# PX4FMUv2_4_6_11.net
KiCad netlist of a schematic drawn in Altium Designer
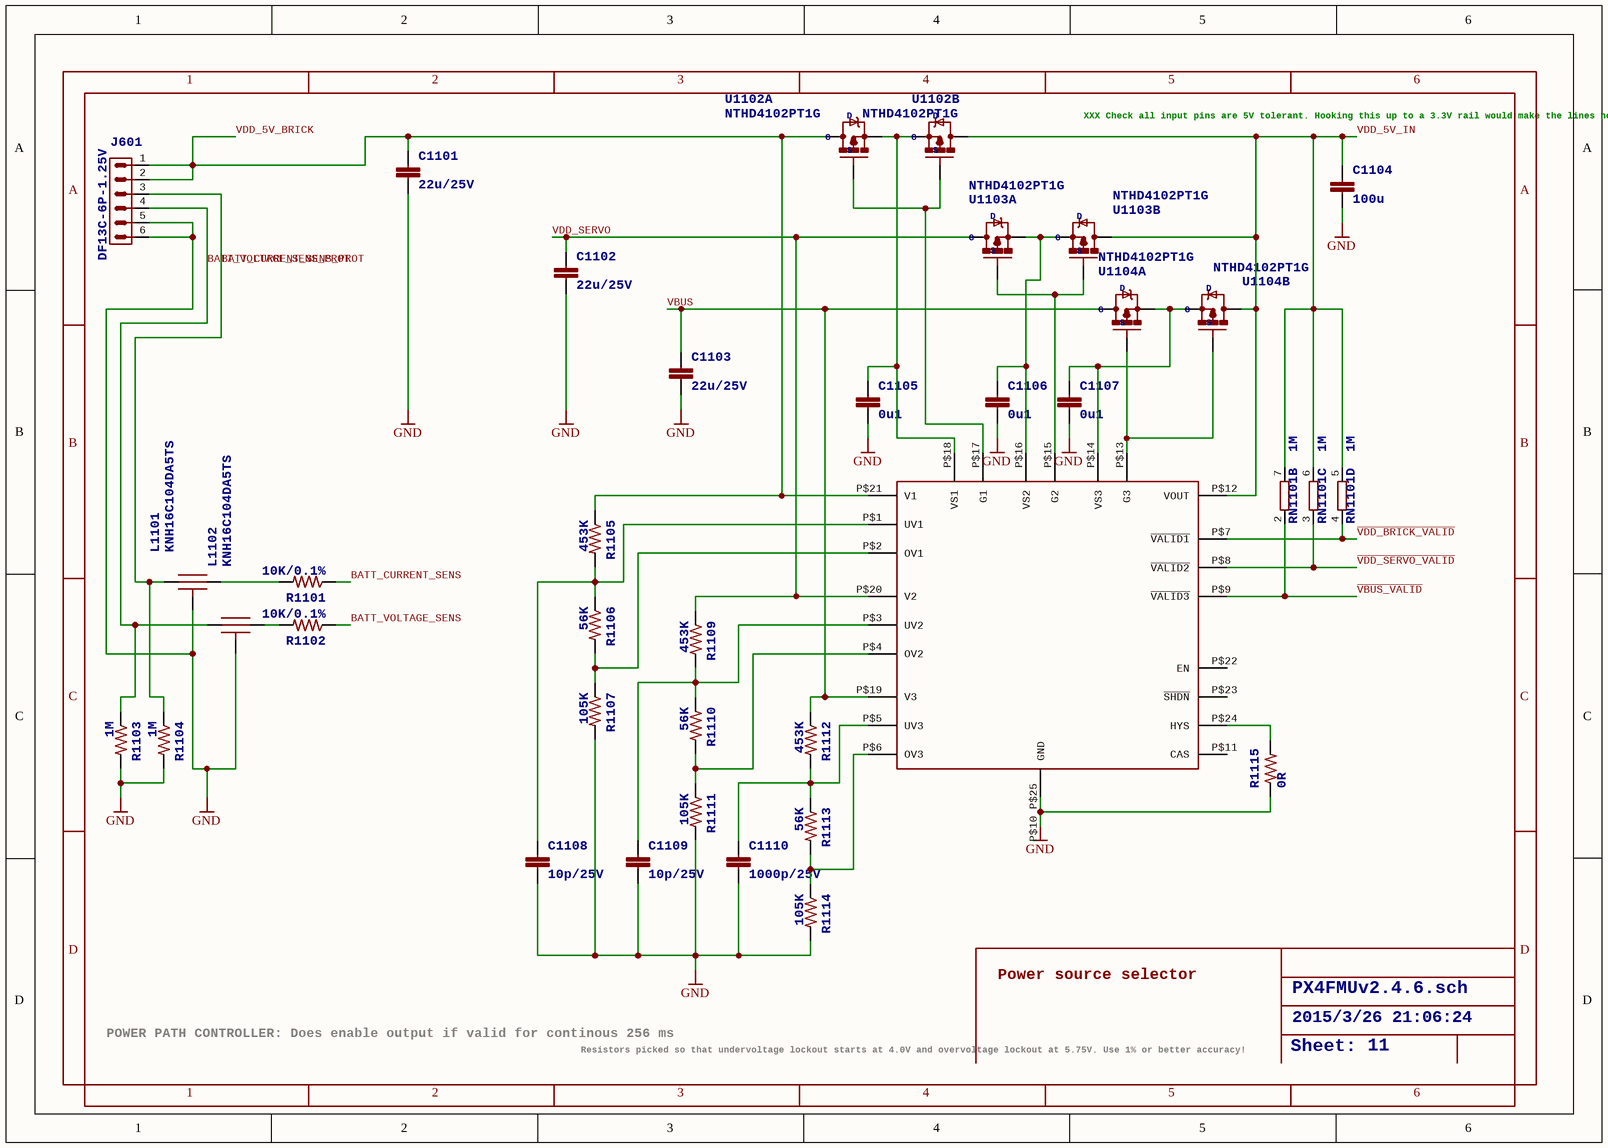
[diagram p0: PX4FMUv2.4.6_11.SchDoc]

(export (version "E")
  (design (tool "Eeschema 10.0.6"))
  (components
    (comp (ref "C1101")
      (value "22u/25V")
      (footprint "0805-CAP")
      (description "<b>Capacitor</b>\nStandard 0603 ceramic capacitor, and 0.1\" leaded capacitor.")
      (fields (field (name "PARTNO") "CL21A226MAQNNNE"))
      (libsource (lib "pixhawk2") (part "CAP0805"))
    )
    (comp (ref "C1102")
      (value "22u/25V")
      (footprint "0805-CAP")
      (description "<b>Capacitor</b>\nStandard 0603 ceramic capacitor, and 0.1\" leaded capacitor.")
      (fields (field (name "PARTNO") "CL21A226MAQNNNE"))
      (libsource (lib "pixhawk2") (part "CAP0805"))
    )
    (comp (ref "C1103")
      (value "22u/25V")
      (footprint "0805-CAP")
      (description "<b>Capacitor</b>\nStandard 0603 ceramic capacitor, and 0.1\" leaded capacitor.")
      (fields (field (name "PARTNO") "CL21A226MAQNNNE"))
      (libsource (lib "pixhawk2") (part "CAP0805"))
    )
    (comp (ref "C1104")
      (value "100u")
      (footprint "1206-CAP")
      (description "<b>Capacitor</b>\nStandard 0603 ceramic capacitor, and 0.1\" leaded capacitor.")
      (fields (field (name "PARTNO") "C3216X5R1A107M160AC"))
      (libsource (lib "pixhawk2") (part "CAP1206"))
    )
    (comp (ref "C1105")
      (value "0u1")
      (footprint "0402-CAP")
      (description "<b>Capacitor</b>\nStandard 0603 ceramic capacitor, and 0.1\" leaded capacitor.")
      (fields (field (name "PARTNO") "C1005X7R1E104K050BB"))
      (libsource (lib "pixhawk2") (part "CAP0402"))
    )
    (comp (ref "C1106")
      (value "0u1")
      (footprint "0402-CAP")
      (description "<b>Capacitor</b>\nStandard 0603 ceramic capacitor, and 0.1\" leaded capacitor.")
      (fields (field (name "PARTNO") "C1005X7R1E104K050BB"))
      (libsource (lib "pixhawk2") (part "CAP0402"))
    )
    (comp (ref "C1107")
      (value "0u1")
      (footprint "0402-CAP")
      (description "<b>Capacitor</b>\nStandard 0603 ceramic capacitor, and 0.1\" leaded capacitor.")
      (fields (field (name "PARTNO") "C1005X7R1E104K050BB"))
      (libsource (lib "pixhawk2") (part "CAP0402"))
    )
    (comp (ref "C1108")
      (value "10p/25V")
      (footprint "0402-CAP")
      (description "<b>Capacitor</b>\nStandard 0603 ceramic capacitor, and 0.1\" leaded capacitor.")
      (fields (field (name "PARTNO") "C0402C100J3GACTU"))
      (libsource (lib "pixhawk2") (part "CAP0402"))
    )
    (comp (ref "C1109")
      (value "10p/25V")
      (footprint "0402-CAP")
      (description "<b>Capacitor</b>\nStandard 0603 ceramic capacitor, and 0.1\" leaded capacitor.")
      (fields (field (name "PARTNO") "C0402C100J3GACTU"))
      (libsource (lib "pixhawk2") (part "CAP0402"))
    )
    (comp (ref "C1110")
      (value "1000p/25V")
      (footprint "0402-CAP")
      (description "<b>Capacitor</b>\nStandard 0603 ceramic capacitor, and 0.1\" leaded capacitor.")
      (fields (field (name "PARTNO") "GRM1555C1E102JA01D"))
      (libsource (lib "pixhawk2") (part "CAP0402"))
    )
    (comp (ref "J601")
      (value "DF13C-6P-1.25V")
      (footprint "DF13C-6P-1.25V")
      (description "DF13-6P\n1.25mm Pitch Miniature Crimping Connector.")
      (libsource (lib "con-hirose-df13") (part "DF13-6P-1.25V"))
    )
    (comp (ref "L1101")
      (value "KNH16C104DA5TS")
      (footprint "KYOCERA-KNH16-DA")
      (description "Kyocera KNH16C104DA5TS EMI filter")
      (libsource (lib "pixhawk2") (part "KNH16C104DA5TS"))
    )
    (comp (ref "L1102")
      (value "KNH16C104DA5TS")
      (footprint "KYOCERA-KNH16-DA")
      (description "Kyocera KNH16C104DA5TS EMI filter")
      (libsource (lib "pixhawk2") (part "KNH16C104DA5TS"))
    )
    (comp (ref "R1101")
      (value "10K/0.1%")
      (footprint "0402-RES")
      (fields (field (name "PARTNO") "ERA-2AEB103X"))
      (libsource (lib "pixhawk2") (part "RESISTOR0402-RES"))
    )
    (comp (ref "R1102")
      (value "10K/0.1%")
      (footprint "0402-RES")
      (fields (field (name "PARTNO") "ERA-2AEB103X"))
      (libsource (lib "pixhawk2") (part "RESISTOR0402-RES"))
    )
    (comp (ref "R1103")
      (value "1M")
      (footprint "0402-RES")
      (fields (field (name "PARTNO") "RC0402FR-071ML"))
      (libsource (lib "pixhawk2") (part "RESISTOR0402-RES"))
    )
    (comp (ref "R1104")
      (value "1M")
      (footprint "0402-RES")
      (fields (field (name "PARTNO") "RC0402FR-071ML"))
      (libsource (lib "pixhawk2") (part "RESISTOR0402-RES"))
    )
    (comp (ref "R1105")
      (value "453K")
      (footprint "0402-RES")
      (fields (field (name "PARTNO") "RMCF0402FT453K"))
      (libsource (lib "pixhawk2") (part "RESISTOR0402-RES"))
    )
    (comp (ref "R1106")
      (value "56K")
      (footprint "0402-RES")
      (fields (field (name "PARTNO") "ERA-2AEB563X"))
      (libsource (lib "pixhawk2") (part "RESISTOR0402-RES"))
    )
    (comp (ref "R1107")
      (value "105K")
      (footprint "0402-RES")
      (fields (field (name "PARTNO") "ERJ-2RKF1053X"))
      (libsource (lib "pixhawk2") (part "RESISTOR0402-RES"))
    )
    (comp (ref "R1109")
      (value "453K")
      (footprint "0402-RES")
      (fields (field (name "PARTNO") "RMCF0402FT453K"))
      (libsource (lib "pixhawk2") (part "RESISTOR0402-RES"))
    )
    (comp (ref "R1110")
      (value "56K")
      (footprint "0402-RES")
      (fields (field (name "PARTNO") "ERA-2AEB563X"))
      (libsource (lib "pixhawk2") (part "RESISTOR0402-RES"))
    )
    (comp (ref "R1111")
      (value "105K")
      (footprint "0402-RES")
      (fields (field (name "PARTNO") "ERJ-2RKF1053X"))
      (libsource (lib "pixhawk2") (part "RESISTOR0402-RES"))
    )
    (comp (ref "R1112")
      (value "453K")
      (footprint "0402-RES")
      (fields (field (name "PARTNO") "RMCF0402FT453K"))
      (libsource (lib "pixhawk2") (part "RESISTOR0402-RES"))
    )
    (comp (ref "R1113")
      (value "56K")
      (footprint "0402-RES")
      (fields (field (name "PARTNO") "ERA-2AEB563X"))
      (libsource (lib "pixhawk2") (part "RESISTOR0402-RES"))
    )
    (comp (ref "R1114")
      (value "105K")
      (footprint "0402-RES")
      (fields (field (name "PARTNO") "ERJ-2RKF1053X"))
      (libsource (lib "pixhawk2") (part "RESISTOR0402-RES"))
    )
    (comp (ref "R1115")
      (value "0R")
      (footprint "0402-RES")
      (fields (field (name "PARTNO") "ERJ-2GE0R00X"))
      (libsource (lib "pixhawk2") (part "RESISTOR0402-RES"))
    )
    (comp (ref "RN1101")
      (value "1M")
      (footprint "EXB28V")
      (description "<b>Array Chip Resistor</b><p>\nSource: RS Component / Phycomp")
      (fields (field (name "PARTNO") "EXB-28V105JX"))
      (libsource (lib "resistor-dil") (part "4R-NEXB28V"))
    )
    (comp (ref "U1101")
      (value "LTC4417")
      (footprint "MO-220")
      (fields (field (name "PARTNO") "LTC4417IUF#PBF"))
      (libsource (lib "pixhawk2") (part "LTC4117"))
    )
    (comp (ref "U1102")
      (value "NTHD4102PT1G")
      (footprint "1206-8")
      (fields (field (name "D") "D") (field (name "S") "S") (field (name "G") "G"))
      (libsource (lib "") (part "MOSFET-DUAL-PCHANNEL-CHIPFET_1"))
    )
    (comp (ref "U1103")
      (value "NTHD4102PT1G")
      (footprint "1206-8")
      (fields (field (name "D") "D") (field (name "S") "S") (field (name "G") "G"))
      (libsource (lib "") (part "MOSFET-DUAL-PCHANNEL-CHIPFET_1"))
    )
    (comp (ref "U1104")
      (value "NTHD4102PT1G")
      (footprint "1206-8")
      (fields (field (name "D") "D") (field (name "S") "S") (field (name "G") "G"))
      (libsource (lib "") (part "MOSFET-DUAL-PCHANNEL-CHIPFET_1"))
    )
  )
  (nets
    (net (code "1") (name "/BATT_CURRENT_SENS") (class "Default")
      (node (ref "R1101") (pin "P$1") (pinfunction "1_P$1") (pintype "passive"))
    )
    (net (code "2") (name "/BATT_CURRENT_SENS_PROT") (class "Default")
      (node (ref "J601") (pin "3") (pinfunction "3_3") (pintype "passive"))
      (node (ref "L1101") (pin "P$1") (pinfunction "P$1_P$1") (pintype "passive"))
      (node (ref "R1104") (pin "P$1") (pinfunction "1_P$1") (pintype "passive"))
    )
    (net (code "3") (name "/BATT_VOLTAGE_SENS") (class "Default")
      (node (ref "R1102") (pin "P$1") (pinfunction "1_P$1") (pintype "passive"))
    )
    (net (code "4") (name "/BATT_VOLTAGE_SENS_PROT") (class "Default")
      (node (ref "J601") (pin "4") (pinfunction "4_4") (pintype "passive"))
      (node (ref "L1102") (pin "P$1") (pinfunction "P$1_P$1") (pintype "passive"))
      (node (ref "R1103") (pin "P$1") (pinfunction "1_P$1") (pintype "passive"))
    )
    (net (code "5") (name "/VBUS") (class "Default")
      (node (ref "C1103") (pin "P$1") (pinfunction "1_P$1") (pintype "passive"))
      (node (ref "R1112") (pin "P$1") (pinfunction "1_P$1") (pintype "passive"))
      (node (ref "U1101") (pin "P$19") (pinfunction "V3_P$19") (pintype "passive"))
      (node (ref "U1104") (pin "P$7_P$8") (pinfunction "D_P$7_P$8") (pintype "passive"))
    )
    (net (code "6") (name "/VDD_5V_BRICK") (class "Default")
      (node (ref "C1101") (pin "P$1") (pinfunction "1_P$1") (pintype "passive"))
      (node (ref "J601") (pin "1") (pinfunction "1_1") (pintype "passive"))
      (node (ref "J601") (pin "2") (pinfunction "2_2") (pintype "passive"))
      (node (ref "R1105") (pin "P$1") (pinfunction "1_P$1") (pintype "passive"))
      (node (ref "U1101") (pin "P$21") (pinfunction "V1_P$21") (pintype "passive"))
      (node (ref "U1102") (pin "P$7_P$8") (pinfunction "D_P$7_P$8") (pintype "passive"))
    )
    (net (code "7") (name "/VDD_5V_IN") (class "Default")
      (node (ref "C1104") (pin "P$1") (pinfunction "1_P$1") (pintype "passive"))
      (node (ref "RN1101") (pin "5") (pinfunction "2_5") (pintype "passive"))
      (node (ref "RN1101") (pin "6") (pinfunction "2_6") (pintype "passive"))
      (node (ref "RN1101") (pin "7") (pinfunction "2_7") (pintype "passive"))
      (node (ref "U1101") (pin "P$12") (pinfunction "VOUT_P$12") (pintype "passive"))
      (node (ref "U1102") (pin "P$5_P$6") (pinfunction "D_P$5_P$6") (pintype "passive"))
      (node (ref "U1103") (pin "P$5_P$6") (pinfunction "D_P$5_P$6") (pintype "passive"))
      (node (ref "U1104") (pin "P$5_P$6") (pinfunction "D_P$5_P$6") (pintype "passive"))
    )
    (net (code "8") (name "/VDD_SERVO") (class "Default")
      (node (ref "C1102") (pin "P$1") (pinfunction "1_P$1") (pintype "passive"))
      (node (ref "R1109") (pin "P$1") (pinfunction "1_P$1") (pintype "passive"))
      (node (ref "U1101") (pin "P$20") (pinfunction "V2_P$20") (pintype "passive"))
      (node (ref "U1103") (pin "P$7_P$8") (pinfunction "D_P$7_P$8") (pintype "passive"))
    )
    (net (code "9") (name "/~{VBUS_VALID}") (class "Default")
      (node (ref "RN1101") (pin "2") (pinfunction "1_2") (pintype "passive"))
      (node (ref "U1101") (pin "P$9") (pinfunction "~{VALID3}_P$9") (pintype "passive"))
    )
    (net (code "10") (name "/~{VDD_BRICK_VALID}") (class "Default")
      (node (ref "RN1101") (pin "4") (pinfunction "1_4") (pintype "passive"))
      (node (ref "U1101") (pin "P$7") (pinfunction "~{VALID1}_P$7") (pintype "passive"))
    )
    (net (code "11") (name "/~{VDD_SERVO_VALID}") (class "Default")
      (node (ref "RN1101") (pin "3") (pinfunction "1_3") (pintype "passive"))
      (node (ref "U1101") (pin "P$8") (pinfunction "~{VALID2}_P$8") (pintype "passive"))
    )
    (net (code "12") (name "GND") (class "Default")
      (node (ref "C1101") (pin "P$2") (pinfunction "2_P$2") (pintype "passive"))
      (node (ref "C1102") (pin "P$2") (pinfunction "2_P$2") (pintype "passive"))
      (node (ref "C1103") (pin "P$2") (pinfunction "2_P$2") (pintype "passive"))
      (node (ref "C1104") (pin "P$2") (pinfunction "2_P$2") (pintype "passive"))
      (node (ref "C1105") (pin "P$2") (pinfunction "2_P$2") (pintype "passive"))
      (node (ref "C1106") (pin "P$2") (pinfunction "2_P$2") (pintype "passive"))
      (node (ref "C1107") (pin "P$2") (pinfunction "2_P$2") (pintype "passive"))
      (node (ref "C1108") (pin "P$2") (pinfunction "2_P$2") (pintype "passive"))
      (node (ref "C1109") (pin "P$2") (pinfunction "2_P$2") (pintype "passive"))
      (node (ref "C1110") (pin "P$2") (pinfunction "2_P$2") (pintype "passive"))
      (node (ref "J601") (pin "5") (pinfunction "5_5") (pintype "passive"))
      (node (ref "J601") (pin "6") (pinfunction "6_6") (pintype "passive"))
      (node (ref "L1101") (pin "P$3_P$4_P$5") (pinfunction "P$3_P$3_P$4_P$5") (pintype "passive"))
      (node (ref "L1102") (pin "P$3_P$4_P$5") (pinfunction "P$3_P$3_P$4_P$5") (pintype "passive"))
      (node (ref "R1103") (pin "P$2") (pinfunction "2_P$2") (pintype "passive"))
      (node (ref "R1104") (pin "P$2") (pinfunction "2_P$2") (pintype "passive"))
      (node (ref "R1107") (pin "P$2") (pinfunction "2_P$2") (pintype "passive"))
      (node (ref "R1111") (pin "P$2") (pinfunction "2_P$2") (pintype "passive"))
      (node (ref "R1114") (pin "P$2") (pinfunction "2_P$2") (pintype "passive"))
      (node (ref "R1115") (pin "P$1") (pinfunction "1_P$1") (pintype "passive"))
      (node (ref "U1101") (pin "P$10_P$25") (pinfunction "GND_P$10_P$25") (pintype "passive"))
    )
    (net (code "13") (name "Net-(C1105-1)") (class "Default")
      (node (ref "C1105") (pin "P$1") (pinfunction "1_P$1") (pintype "passive"))
      (node (ref "U1101") (pin "P$18") (pinfunction "VS1_P$18") (pintype "passive"))
      (node (ref "U1102") (pin "P$1") (pinfunction "S_P$1") (pintype "passive"))
      (node (ref "U1102") (pin "P$3") (pinfunction "S_P$3") (pintype "passive"))
    )
    (net (code "14") (name "Net-(C1106-1)") (class "Default")
      (node (ref "C1106") (pin "P$1") (pinfunction "1_P$1") (pintype "passive"))
      (node (ref "U1101") (pin "P$16") (pinfunction "VS2_P$16") (pintype "passive"))
      (node (ref "U1103") (pin "P$1") (pinfunction "S_P$1") (pintype "passive"))
      (node (ref "U1103") (pin "P$3") (pinfunction "S_P$3") (pintype "passive"))
    )
    (net (code "15") (name "Net-(C1107-1)") (class "Default")
      (node (ref "C1107") (pin "P$1") (pinfunction "1_P$1") (pintype "passive"))
      (node (ref "U1101") (pin "P$14") (pinfunction "VS3_P$14") (pintype "passive"))
      (node (ref "U1104") (pin "P$1") (pinfunction "S_P$1") (pintype "passive"))
      (node (ref "U1104") (pin "P$3") (pinfunction "S_P$3") (pintype "passive"))
    )
    (net (code "16") (name "Net-(C1108-1)") (class "Default")
      (node (ref "C1108") (pin "P$1") (pinfunction "1_P$1") (pintype "passive"))
      (node (ref "R1105") (pin "P$2") (pinfunction "2_P$2") (pintype "passive"))
      (node (ref "R1106") (pin "P$1") (pinfunction "1_P$1") (pintype "passive"))
      (node (ref "U1101") (pin "P$1") (pinfunction "UV1_P$1") (pintype "passive"))
    )
    (net (code "17") (name "Net-(C1109-1)") (class "Default")
      (node (ref "C1109") (pin "P$1") (pinfunction "1_P$1") (pintype "passive"))
      (node (ref "R1109") (pin "P$2") (pinfunction "2_P$2") (pintype "passive"))
      (node (ref "R1110") (pin "P$1") (pinfunction "1_P$1") (pintype "passive"))
      (node (ref "U1101") (pin "P$3") (pinfunction "UV2_P$3") (pintype "passive"))
    )
    (net (code "18") (name "Net-(C1110-1)") (class "Default")
      (node (ref "C1110") (pin "P$1") (pinfunction "1_P$1") (pintype "passive"))
      (node (ref "R1112") (pin "P$2") (pinfunction "2_P$2") (pintype "passive"))
      (node (ref "R1113") (pin "P$1") (pinfunction "1_P$1") (pintype "passive"))
      (node (ref "U1101") (pin "P$5") (pinfunction "UV3_P$5") (pintype "passive"))
    )
    (net (code "19") (name "Net-(R1101-2)") (class "Default")
      (node (ref "L1101") (pin "P$2") (pinfunction "P$2_P$2") (pintype "passive"))
      (node (ref "R1101") (pin "P$2") (pinfunction "2_P$2") (pintype "passive"))
    )
    (net (code "20") (name "Net-(R1102-2)") (class "Default")
      (node (ref "L1102") (pin "P$2") (pinfunction "P$2_P$2") (pintype "passive"))
      (node (ref "R1102") (pin "P$2") (pinfunction "2_P$2") (pintype "passive"))
    )
    (net (code "21") (name "Net-(R1106-2)") (class "Default")
      (node (ref "R1106") (pin "P$2") (pinfunction "2_P$2") (pintype "passive"))
      (node (ref "R1107") (pin "P$1") (pinfunction "1_P$1") (pintype "passive"))
      (node (ref "U1101") (pin "P$2") (pinfunction "OV1_P$2") (pintype "passive"))
    )
    (net (code "22") (name "Net-(R1110-2)") (class "Default")
      (node (ref "R1110") (pin "P$2") (pinfunction "2_P$2") (pintype "passive"))
      (node (ref "R1111") (pin "P$1") (pinfunction "1_P$1") (pintype "passive"))
      (node (ref "U1101") (pin "P$4") (pinfunction "OV2_P$4") (pintype "passive"))
    )
    (net (code "23") (name "Net-(R1113-2)") (class "Default")
      (node (ref "R1113") (pin "P$2") (pinfunction "2_P$2") (pintype "passive"))
      (node (ref "R1114") (pin "P$1") (pinfunction "1_P$1") (pintype "passive"))
      (node (ref "U1101") (pin "P$6") (pinfunction "OV3_P$6") (pintype "passive"))
    )
    (net (code "24") (name "Net-(R1115-2)") (class "Default")
      (node (ref "R1115") (pin "P$2") (pinfunction "2_P$2") (pintype "passive"))
      (node (ref "U1101") (pin "P$24") (pinfunction "HYS_P$24") (pintype "passive"))
    )
    (net (code "25") (name "Net-(U1101-G1)") (class "Default")
      (node (ref "U1101") (pin "P$17") (pinfunction "G1_P$17") (pintype "passive"))
      (node (ref "U1102") (pin "P$2") (pinfunction "G_P$2") (pintype "passive"))
      (node (ref "U1102") (pin "P$4") (pinfunction "G_P$4") (pintype "passive"))
    )
    (net (code "26") (name "Net-(U1101-G2)") (class "Default")
      (node (ref "U1101") (pin "P$15") (pinfunction "G2_P$15") (pintype "passive"))
      (node (ref "U1103") (pin "P$2") (pinfunction "G_P$2") (pintype "passive"))
      (node (ref "U1103") (pin "P$4") (pinfunction "G_P$4") (pintype "passive"))
    )
    (net (code "27") (name "Net-(U1101-G3)") (class "Default")
      (node (ref "U1101") (pin "P$13") (pinfunction "G3_P$13") (pintype "passive"))
      (node (ref "U1104") (pin "P$2") (pinfunction "G_P$2") (pintype "passive"))
      (node (ref "U1104") (pin "P$4") (pinfunction "G_P$4") (pintype "passive"))
    )
    (net (code "28") (name "unconnected-(U1101-CAS-PadP$11)") (class "Default")
      (node (ref "U1101") (pin "P$11") (pinfunction "CAS_P$11") (pintype "passive"))
    )
    (net (code "29") (name "unconnected-(U1101-EN-PadP$22)") (class "Default")
      (node (ref "U1101") (pin "P$22") (pinfunction "EN_P$22") (pintype "passive"))
    )
    (net (code "30") (name "unconnected-(U1101-~{SHDN}-PadP$23)") (class "Default")
      (node (ref "U1101") (pin "P$23") (pinfunction "~{SHDN}_P$23") (pintype "passive"))
    )
  )
)
